# Sheet1.net
KiCad netlist of a schematic drawn in Altium Designer
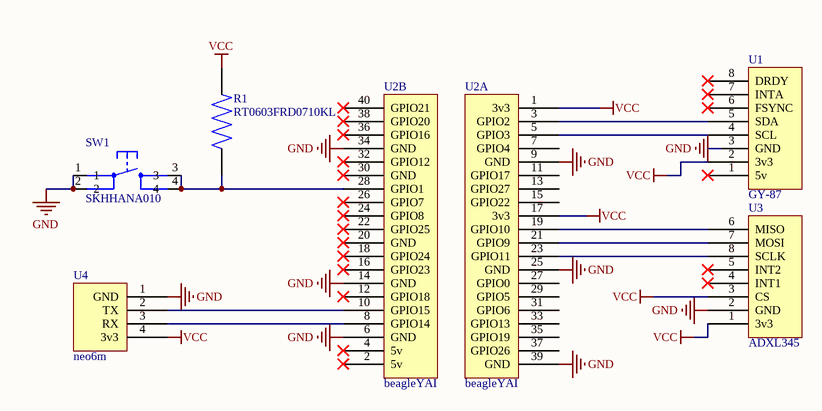
[diagram p0: Sheet1.SchDoc]

(export (version "E")
  (design (tool "Eeschema 10.0.6"))
  (components
    (comp (ref "R1")
      (value "RT0603FRD0710KL")
      (footprint "RESC1608X55N")
      (description "Res Thin Film 0603 10K Ohm 1% 0.1W(1/10W) Â±25ppm/C Molded SMD Paper T/R")
      (fields (field (name "MF") "Yageo"))
      (libsource (lib "Schlib1") (part "RT0603FRD0710KL"))
    )
    (comp (ref "SW1")
      (value "SKHHANA010")
      (footprint "SW_SKHHANA010")
      (description "Switch Tactile N.O. SPST Round Button PC Pins 0.05A 12VDC 0.98N Thru-Hole Bulk")
      (fields (field (name "MF") "ALPS"))
      (libsource (lib "Schlib1") (part "SKHHANA010"))
    )
    (comp (ref "U1")
      (value "GY-87")
      (footprint "single8pinfemale")
      (libsource (lib "Schlib1") (part "GY-87"))
    )
    (comp (ref "U2")
      (value "beagleYAI")
      (footprint "40pinfemale")
      (libsource (lib "Schlib1") (part "beagleYAI"))
    )
    (comp (ref "U3")
      (value "ADXL345")
      (footprint "single8pinfemale")
      (libsource (lib "Schlib1") (part "ADXL345"))
    )
    (comp (ref "U4")
      (value "neo6m")
      (footprint "single4pinfemale")
      (libsource (lib "Schlib1") (part "neo6m"))
    )
  )
  (nets
    (net (code "1") (name "GND") (class "Default")
      (node (ref "SW1") (pin "1") (pinfunction "1_1") (pintype "passive"))
      (node (ref "SW1") (pin "2") (pinfunction "2_2") (pintype "passive"))
      (node (ref "U1") (pin "3") (pinfunction "GND_3") (pintype "passive"))
      (node (ref "U2") (pin "14") (pinfunction "GND_14") (pintype "power_in"))
      (node (ref "U2") (pin "25") (pinfunction "GND_25") (pintype "power_in"))
      (node (ref "U2") (pin "34") (pinfunction "GND_34") (pintype "power_in"))
      (node (ref "U2") (pin "39") (pinfunction "GND_39") (pintype "power_in"))
      (node (ref "U2") (pin "6") (pinfunction "GND_6") (pintype "power_in"))
      (node (ref "U2") (pin "9") (pinfunction "GND_9") (pintype "power_in"))
      (node (ref "U3") (pin "2") (pinfunction "GND_2") (pintype "power_in"))
      (node (ref "U4") (pin "1") (pinfunction "GND_1") (pintype "power_in"))
    )
    (net (code "2") (name "Net-(U1-SCL)") (class "Default")
      (node (ref "U1") (pin "4") (pinfunction "SCL_4") (pintype "passive"))
      (node (ref "U2") (pin "5") (pinfunction "GPIO3_5") (pintype "passive"))
    )
    (net (code "3") (name "Net-(U1-SDA)") (class "Default")
      (node (ref "U1") (pin "5") (pinfunction "SDA_5") (pintype "passive"))
      (node (ref "U2") (pin "3") (pinfunction "GPIO2_3") (pintype "passive"))
    )
    (net (code "4") (name "Net-(U2A-GPIO9)") (class "Default")
      (node (ref "U2") (pin "21") (pinfunction "GPIO9_21") (pintype "passive"))
      (node (ref "U3") (pin "7") (pinfunction "MOSI_7") (pintype "passive"))
    )
    (net (code "5") (name "Net-(U2A-GPIO10)") (class "Default")
      (node (ref "U2") (pin "19") (pinfunction "GPIO10_19") (pintype "passive"))
      (node (ref "U3") (pin "6") (pinfunction "MISO_6") (pintype "passive"))
    )
    (net (code "6") (name "Net-(U2A-GPIO11)") (class "Default")
      (node (ref "U2") (pin "23") (pinfunction "GPIO11_23") (pintype "passive"))
      (node (ref "U3") (pin "8") (pinfunction "SCLK_8") (pintype "passive"))
    )
    (net (code "7") (name "Net-(U2B-GPIO1)") (class "Default")
      (node (ref "R1") (pin "1") (pinfunction "1_1") (pintype "passive"))
      (node (ref "SW1") (pin "3") (pinfunction "3_3") (pintype "passive"))
      (node (ref "SW1") (pin "4") (pinfunction "4_4") (pintype "passive"))
      (node (ref "U2") (pin "28") (pinfunction "GPIO1_28") (pintype "passive"))
    )
    (net (code "8") (name "Net-(U2B-GPIO14)") (class "Default")
      (node (ref "U2") (pin "8") (pinfunction "GPIO14_8") (pintype "passive"))
      (node (ref "U4") (pin "3") (pinfunction "RX_3") (pintype "passive"))
    )
    (net (code "9") (name "Net-(U2B-GPIO15)") (class "Default")
      (node (ref "U2") (pin "10") (pinfunction "GPIO15_10") (pintype "passive"))
      (node (ref "U4") (pin "2") (pinfunction "TX_2") (pintype "passive"))
    )
    (net (code "10") (name "VCC") (class "Default")
      (node (ref "R1") (pin "2") (pinfunction "2_2") (pintype "passive"))
      (node (ref "U1") (pin "2") (pinfunction "3v3_2") (pintype "passive"))
      (node (ref "U2") (pin "1") (pinfunction "3v3_1") (pintype "power_in"))
      (node (ref "U2") (pin "17") (pinfunction "3v3_17") (pintype "power_in"))
      (node (ref "U3") (pin "1") (pinfunction "3v3_1") (pintype "power_in"))
      (node (ref "U3") (pin "3") (pinfunction "CS_3") (pintype "passive"))
      (node (ref "U4") (pin "4") (pinfunction "3v3_4") (pintype "power_in"))
    )
    (net (code "11") (name "unconnected-(U1-5v-Pad1)") (class "Default")
      (node (ref "U1") (pin "1") (pinfunction "5v_1") (pintype "passive+no_connect"))
    )
    (net (code "12") (name "unconnected-(U1-DRDY-Pad8)") (class "Default")
      (node (ref "U1") (pin "8") (pinfunction "DRDY_8") (pintype "passive+no_connect"))
    )
    (net (code "13") (name "unconnected-(U1-FSYNC-Pad6)") (class "Default")
      (node (ref "U1") (pin "6") (pinfunction "FSYNC_6") (pintype "passive+no_connect"))
    )
    (net (code "14") (name "unconnected-(U1-INTA-Pad7)") (class "Default")
      (node (ref "U1") (pin "7") (pinfunction "INTA_7") (pintype "passive+no_connect"))
    )
    (net (code "15") (name "unconnected-(U2A-GPIO0-Pad27)") (class "Default")
      (node (ref "U2") (pin "27") (pinfunction "GPIO0_27") (pintype "passive"))
    )
    (net (code "16") (name "unconnected-(U2A-GPIO4-Pad7)") (class "Default")
      (node (ref "U2") (pin "7") (pinfunction "GPIO4_7") (pintype "passive"))
    )
    (net (code "17") (name "unconnected-(U2A-GPIO5-Pad29)") (class "Default")
      (node (ref "U2") (pin "29") (pinfunction "GPIO5_29") (pintype "passive"))
    )
    (net (code "18") (name "unconnected-(U2A-GPIO6-Pad31)") (class "Default")
      (node (ref "U2") (pin "31") (pinfunction "GPIO6_31") (pintype "passive"))
    )
    (net (code "19") (name "unconnected-(U2A-GPIO13-Pad33)") (class "Default")
      (node (ref "U2") (pin "33") (pinfunction "GPIO13_33") (pintype "passive"))
    )
    (net (code "20") (name "unconnected-(U2A-GPIO17-Pad11)") (class "Default")
      (node (ref "U2") (pin "11") (pinfunction "GPIO17_11") (pintype "passive"))
    )
    (net (code "21") (name "unconnected-(U2A-GPIO19-Pad35)") (class "Default")
      (node (ref "U2") (pin "35") (pinfunction "GPIO19_35") (pintype "passive"))
    )
    (net (code "22") (name "unconnected-(U2A-GPIO22-Pad15)") (class "Default")
      (node (ref "U2") (pin "15") (pinfunction "GPIO22_15") (pintype "passive"))
    )
    (net (code "23") (name "unconnected-(U2A-GPIO26-Pad37)") (class "Default")
      (node (ref "U2") (pin "37") (pinfunction "GPIO26_37") (pintype "passive"))
    )
    (net (code "24") (name "unconnected-(U2A-GPIO27-Pad13)") (class "Default")
      (node (ref "U2") (pin "13") (pinfunction "GPIO27_13") (pintype "passive"))
    )
    (net (code "25") (name "unconnected-(U2B-5v-Pad2)") (class "Default")
      (node (ref "U2") (pin "2") (pinfunction "5v_2") (pintype "power_in+no_connect"))
    )
    (net (code "26") (name "unconnected-(U2B-5v-Pad4)") (class "Default")
      (node (ref "U2") (pin "4") (pinfunction "5v_4") (pintype "power_in+no_connect"))
    )
    (net (code "27") (name "unconnected-(U2B-GND-Pad20)") (class "Default")
      (node (ref "U2") (pin "20") (pinfunction "GND_20") (pintype "power_in+no_connect"))
    )
    (net (code "28") (name "unconnected-(U2B-GND-Pad30)") (class "Default")
      (node (ref "U2") (pin "30") (pinfunction "GND_30") (pintype "power_in+no_connect"))
    )
    (net (code "29") (name "unconnected-(U2B-GPIO7-Pad26)") (class "Default")
      (node (ref "U2") (pin "26") (pinfunction "GPIO7_26") (pintype "passive+no_connect"))
    )
    (net (code "30") (name "unconnected-(U2B-GPIO8-Pad24)") (class "Default")
      (node (ref "U2") (pin "24") (pinfunction "GPIO8_24") (pintype "passive+no_connect"))
    )
    (net (code "31") (name "unconnected-(U2B-GPIO12-Pad32)") (class "Default")
      (node (ref "U2") (pin "32") (pinfunction "GPIO12_32") (pintype "passive+no_connect"))
    )
    (net (code "32") (name "unconnected-(U2B-GPIO16-Pad36)") (class "Default")
      (node (ref "U2") (pin "36") (pinfunction "GPIO16_36") (pintype "passive+no_connect"))
    )
    (net (code "33") (name "unconnected-(U2B-GPIO18-Pad12)") (class "Default")
      (node (ref "U2") (pin "12") (pinfunction "GPIO18_12") (pintype "passive+no_connect"))
    )
    (net (code "34") (name "unconnected-(U2B-GPIO20-Pad38)") (class "Default")
      (node (ref "U2") (pin "38") (pinfunction "GPIO20_38") (pintype "passive+no_connect"))
    )
    (net (code "35") (name "unconnected-(U2B-GPIO21-Pad40)") (class "Default")
      (node (ref "U2") (pin "40") (pinfunction "GPIO21_40") (pintype "passive+no_connect"))
    )
    (net (code "36") (name "unconnected-(U2B-GPIO23-Pad16)") (class "Default")
      (node (ref "U2") (pin "16") (pinfunction "GPIO23_16") (pintype "passive+no_connect"))
    )
    (net (code "37") (name "unconnected-(U2B-GPIO24-Pad18)") (class "Default")
      (node (ref "U2") (pin "18") (pinfunction "GPIO24_18") (pintype "passive+no_connect"))
    )
    (net (code "38") (name "unconnected-(U2B-GPIO25-Pad22)") (class "Default")
      (node (ref "U2") (pin "22") (pinfunction "GPIO25_22") (pintype "passive+no_connect"))
    )
    (net (code "39") (name "unconnected-(U3-INT1-Pad4)") (class "Default")
      (node (ref "U3") (pin "4") (pinfunction "INT1_4") (pintype "passive+no_connect"))
    )
    (net (code "40") (name "unconnected-(U3-INT2-Pad5)") (class "Default")
      (node (ref "U3") (pin "5") (pinfunction "INT2_5") (pintype "passive+no_connect"))
    )
  )
)
